# dp_tsc_com-v1_21.net
KiCad netlist of a schematic drawn in EAGLE
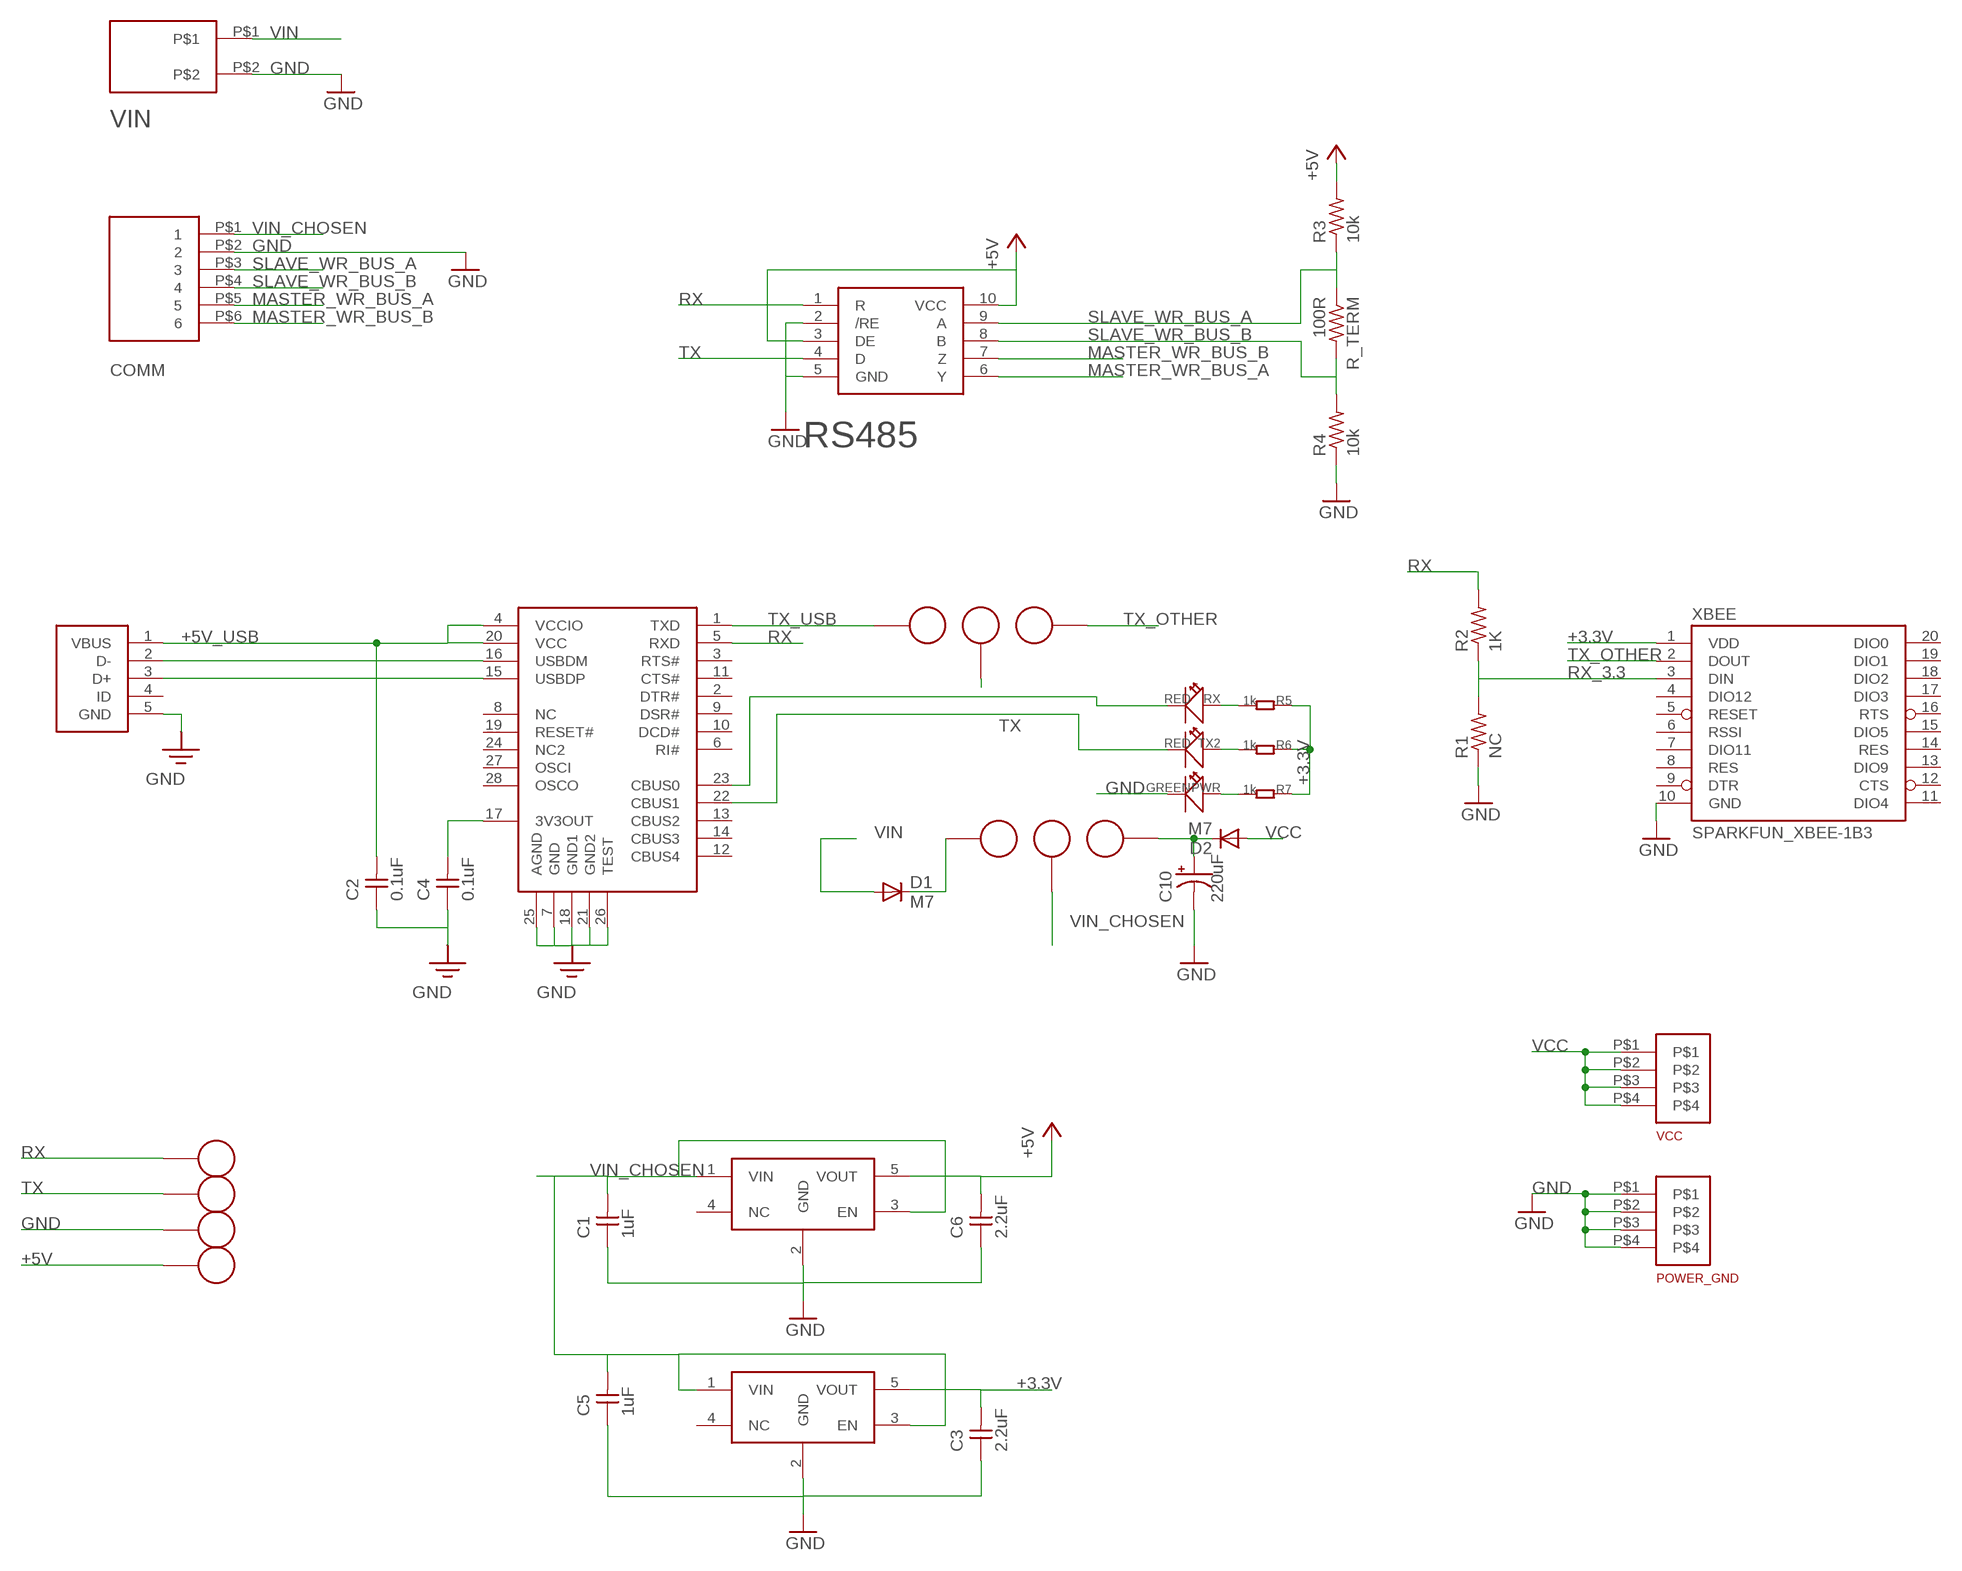
[diagram p0: schematic, sheet 1]

(export (version "E")
  (design (tool "Eeschema 10.0.6"))
  (components
    (comp (ref "+5V")
      (value "CONNECTOR_TV")
      (footprint "eagle-import:CONNECTOR_TV")
      (libsource (lib "eagle-import") (part "CONNECTOR_TV"))
    )
    (comp (ref "3.3V_REG")
      (value "MIC5235")
      (footprint "eagle-import:SOT-23-5")
      (libsource (lib "eagle-import") (part "MIC5235"))
    )
    (comp (ref "5V1")
      (value "CONNECTOR_TV")
      (footprint "eagle-import:CONNECTOR_TV")
      (libsource (lib "eagle-import") (part "CONNECTOR_TV"))
    )
    (comp (ref "5V_REG")
      (value "MIC5235")
      (footprint "eagle-import:SOT-23-5")
      (libsource (lib "eagle-import") (part "MIC5235"))
    )
    (comp (ref "5V_USB1")
      (value "CONNECTOR_TV")
      (footprint "eagle-import:CONNECTOR_TV")
      (libsource (lib "eagle-import") (part "CONNECTOR_TV"))
    )
    (comp (ref "5V_VREG1")
      (value "CONNECTOR_TV")
      (footprint "eagle-import:CONNECTOR_TV")
      (libsource (lib "eagle-import") (part "CONNECTOR_TV"))
    )
    (comp (ref "C1")
      (value "1uF")
      (footprint "eagle-import:0805@1")
      (libsource (lib "eagle-import") (part "CAPACITOR0805"))
    )
    (comp (ref "C2")
      (value "0.1uF")
      (footprint "eagle-import:0805@1")
      (libsource (lib "eagle-import") (part "CAPACITOR0805"))
    )
    (comp (ref "C3")
      (value "2.2uF")
      (footprint "eagle-import:0805@1")
      (libsource (lib "eagle-import") (part "CAPACITOR0805"))
    )
    (comp (ref "C4")
      (value "0.1uF")
      (footprint "eagle-import:0805@1")
      (libsource (lib "eagle-import") (part "CAPACITOR0805"))
    )
    (comp (ref "C5")
      (value "1uF")
      (footprint "eagle-import:0805@1")
      (libsource (lib "eagle-import") (part "CAPACITOR0805"))
    )
    (comp (ref "C6")
      (value "2.2uF")
      (footprint "eagle-import:0805@1")
      (libsource (lib "eagle-import") (part "CAPACITOR0805"))
    )
    (comp (ref "C10")
      (value "220uF")
      (footprint "eagle-import:HAO")
      (libsource (lib "eagle-import") (part "CAP-EMVY350ADA221MHA0G"))
    )
    (comp (ref "COMM")
      (value "6PIN-RIBBONCABLE-BOARDHEADER")
      (footprint "eagle-import:6PIN-HEADER-DUALROW")
      (libsource (lib "eagle-import") (part "6PIN-RIBBONCABLE-BOARDHEADER"))
    )
    (comp (ref "D1")
      (value "M7")
      (footprint "eagle-import:DO214BA")
      (libsource (lib "eagle-import") (part "DIODE-DO214BA"))
    )
    (comp (ref "D2")
      (value "M7")
      (footprint "eagle-import:DO214BA")
      (libsource (lib "eagle-import") (part "DIODE-DO214BA"))
    )
    (comp (ref "FT323R")
      (value "FT232R")
      (footprint "eagle-import:SSOP-28")
      (libsource (lib "eagle-import") (part "FT232R"))
    )
    (comp (ref "GND")
      (value "CONNECTOR_TV")
      (footprint "eagle-import:CONNECTOR_TV")
      (libsource (lib "eagle-import") (part "CONNECTOR_TV"))
    )
    (comp (ref "POWER_GND")
      (value "SCREW_TERMINAL_7700K")
      (footprint "eagle-import:SCREW_TERM_7700K")
      (libsource (lib "eagle-import") (part "SCREW_TERMINAL_7700K"))
    )
    (comp (ref "PWR")
      (value "GREEN")
      (footprint "eagle-import:LED0603_S")
      (libsource (lib "eagle-import") (part "LED0603_SS"))
    )
    (comp (ref "R1")
      (value "NC")
      (footprint "eagle-import:0603")
      (libsource (lib "eagle-import") (part "RESISTOR0603"))
    )
    (comp (ref "R2")
      (value "1K")
      (footprint "eagle-import:0603")
      (libsource (lib "eagle-import") (part "RESISTOR0603"))
    )
    (comp (ref "R3")
      (value "10k")
      (footprint "eagle-import:0603")
      (libsource (lib "eagle-import") (part "RESISTOR0603"))
    )
    (comp (ref "R4")
      (value "10k")
      (footprint "eagle-import:0603")
      (libsource (lib "eagle-import") (part "RESISTOR0603"))
    )
    (comp (ref "R5")
      (value "1k")
      (footprint "eagle-import:0603_S")
      (libsource (lib "eagle-import") (part "R0603_S"))
    )
    (comp (ref "R6")
      (value "1k")
      (footprint "eagle-import:0603_S")
      (libsource (lib "eagle-import") (part "R0603_S"))
    )
    (comp (ref "R7")
      (value "1k")
      (footprint "eagle-import:0603_S")
      (libsource (lib "eagle-import") (part "R0603_S"))
    )
    (comp (ref "RS485")
      (value "RS485-SN65HVD3086EDGSR")
      (footprint "eagle-import:MSOP-10")
      (libsource (lib "eagle-import") (part "RS485-SN65HVD3086EDGSR"))
    )
    (comp (ref "RX")
      (value "RED")
      (footprint "eagle-import:LED0603_S")
      (libsource (lib "eagle-import") (part "LED0603_SS"))
    )
    (comp (ref "RX1")
      (value "CONNECTOR_TV")
      (footprint "eagle-import:CONNECTOR_TV")
      (libsource (lib "eagle-import") (part "CONNECTOR_TV"))
    )
    (comp (ref "R_TERM")
      (value "100R")
      (footprint "eagle-import:0603")
      (libsource (lib "eagle-import") (part "RESISTOR0603"))
    )
    (comp (ref "TX")
      (value "CONNECTOR_TV")
      (footprint "eagle-import:CONNECTOR_TV")
      (libsource (lib "eagle-import") (part "CONNECTOR_TV"))
    )
    (comp (ref "TX1")
      (value "CONNECTOR_TV")
      (footprint "eagle-import:CONNECTOR_TV")
      (libsource (lib "eagle-import") (part "CONNECTOR_TV"))
    )
    (comp (ref "TX2")
      (value "RED")
      (footprint "eagle-import:LED0603_S")
      (libsource (lib "eagle-import") (part "LED0603_SS"))
    )
    (comp (ref "TX_FTDI")
      (value "CONNECTOR_TV")
      (footprint "eagle-import:CONNECTOR_TV")
      (libsource (lib "eagle-import") (part "CONNECTOR_TV"))
    )
    (comp (ref "TX_TTL")
      (value "CONNECTOR_TV")
      (footprint "eagle-import:CONNECTOR_TV")
      (libsource (lib "eagle-import") (part "CONNECTOR_TV"))
    )
    (comp (ref "USB")
      (value "MINIUSB")
      (footprint "eagle-import:UX60-MINI-USB")
      (libsource (lib "eagle-import") (part "MINIUSB"))
    )
    (comp (ref "VCC")
      (value "SCREW_TERMINAL_7700K")
      (footprint "eagle-import:SCREW_TERM_7700K")
      (libsource (lib "eagle-import") (part "SCREW_TERMINAL_7700K"))
    )
    (comp (ref "VIN")
      (value "2PIN-3.81MM-TERMINAL-BLOCK")
      (footprint "eagle-import:2PIN-TERMINAL-BLOCK-SMALLER")
      (libsource (lib "eagle-import") (part "2PIN-3.81MM-TERMINAL-BLOCK"))
    )
    (comp (ref "XBEE")
      (value "SPARKFUN_XBEE-1B3")
      (footprint "eagle-import:SPARKFUN_XBEE-SMD")
      (libsource (lib "eagle-import") (part "SPARKFUN_XBEE-1B3"))
    )
  )
  (nets
    (net (code "1") (name "+5V") (class "Default")
      (node (ref "+5V") (pin "P$1") (pinfunction "P$1_P$1") (pintype "bidirectional"))
      (node (ref "5V_REG") (pin "5") (pinfunction "VOUT_5") (pintype "bidirectional"))
      (node (ref "C6") (pin "2") (pinfunction "2_2") (pintype "passive"))
      (node (ref "R3") (pin "2") (pinfunction "2_2") (pintype "passive"))
      (node (ref "RS485") (pin "10") (pinfunction "VCC_10") (pintype "bidirectional"))
      (node (ref "RS485") (pin "3") (pinfunction "DE_3") (pintype "bidirectional"))
    )
    (net (code "2") (name "/+3.3V") (class "Default")
      (node (ref "3.3V_REG") (pin "5") (pinfunction "VOUT_5") (pintype "bidirectional"))
      (node (ref "C3") (pin "2") (pinfunction "2_2") (pintype "passive"))
      (node (ref "R5") (pin "1") (pinfunction "1_1") (pintype "bidirectional"))
      (node (ref "R6") (pin "1") (pinfunction "1_1") (pintype "bidirectional"))
      (node (ref "R7") (pin "1") (pinfunction "1_1") (pintype "bidirectional"))
      (node (ref "XBEE") (pin "1") (pinfunction "VDD_1") (pintype "power_in"))
    )
    (net (code "3") (name "/+5V_USB") (class "Default")
      (node (ref "C2") (pin "2") (pinfunction "2_2") (pintype "passive"))
      (node (ref "FT323R") (pin "20") (pinfunction "VCC_20") (pintype "bidirectional"))
      (node (ref "FT323R") (pin "4") (pinfunction "VCCIO_4") (pintype "bidirectional"))
      (node (ref "USB") (pin "1") (pinfunction "VBUS_1") (pintype "bidirectional"))
    )
    (net (code "4") (name "/MASTER_WR_BUS_A") (class "Default")
      (node (ref "COMM") (pin "P$5") (pinfunction "5_P$5") (pintype "bidirectional"))
      (node (ref "RS485") (pin "6") (pinfunction "Y_6") (pintype "bidirectional"))
    )
    (net (code "5") (name "/MASTER_WR_BUS_B") (class "Default")
      (node (ref "COMM") (pin "P$6") (pinfunction "6_P$6") (pintype "bidirectional"))
      (node (ref "RS485") (pin "7") (pinfunction "Z_7") (pintype "bidirectional"))
    )
    (net (code "6") (name "/RX") (class "Default")
      (node (ref "FT323R") (pin "5") (pinfunction "RXD_5") (pintype "bidirectional"))
      (node (ref "R2") (pin "2") (pinfunction "2_2") (pintype "passive"))
      (node (ref "RS485") (pin "1") (pinfunction "R_1") (pintype "bidirectional"))
      (node (ref "RX1") (pin "P$1") (pinfunction "P$1_P$1") (pintype "bidirectional"))
    )
    (net (code "7") (name "/RX_3.3") (class "Default")
      (node (ref "R1") (pin "2") (pinfunction "2_2") (pintype "passive"))
      (node (ref "R2") (pin "1") (pinfunction "1_1") (pintype "passive"))
      (node (ref "XBEE") (pin "3") (pinfunction "DIN_3") (pintype "input"))
    )
    (net (code "8") (name "/SLAVE_WR_BUS_A") (class "Default")
      (node (ref "COMM") (pin "P$3") (pinfunction "3_P$3") (pintype "bidirectional"))
      (node (ref "R3") (pin "1") (pinfunction "1_1") (pintype "passive"))
      (node (ref "RS485") (pin "9") (pinfunction "A_9") (pintype "bidirectional"))
      (node (ref "R_TERM") (pin "1") (pinfunction "1_1") (pintype "passive"))
    )
    (net (code "9") (name "/SLAVE_WR_BUS_B") (class "Default")
      (node (ref "COMM") (pin "P$4") (pinfunction "4_P$4") (pintype "bidirectional"))
      (node (ref "R4") (pin "2") (pinfunction "2_2") (pintype "passive"))
      (node (ref "RS485") (pin "8") (pinfunction "B_8") (pintype "bidirectional"))
      (node (ref "R_TERM") (pin "2") (pinfunction "2_2") (pintype "passive"))
    )
    (net (code "10") (name "/TX") (class "Default")
      (node (ref "RS485") (pin "4") (pinfunction "D_4") (pintype "bidirectional"))
      (node (ref "TX") (pin "P$1") (pinfunction "P$1_P$1") (pintype "bidirectional"))
      (node (ref "TX1") (pin "P$1") (pinfunction "P$1_P$1") (pintype "bidirectional"))
    )
    (net (code "11") (name "/TX_OTHER") (class "Default")
      (node (ref "TX_TTL") (pin "P$1") (pinfunction "P$1_P$1") (pintype "bidirectional"))
      (node (ref "XBEE") (pin "2") (pinfunction "DOUT_2") (pintype "output"))
    )
    (net (code "12") (name "/TX_USB") (class "Default")
      (node (ref "FT323R") (pin "1") (pinfunction "TXD_1") (pintype "bidirectional"))
      (node (ref "TX_FTDI") (pin "P$1") (pinfunction "P$1_P$1") (pintype "bidirectional"))
    )
    (net (code "13") (name "/VCC") (class "Default")
      (node (ref "D2") (pin "A") (pinfunction "A_A") (pintype "passive"))
      (node (ref "VCC") (pin "P$1") (pinfunction "P$1_P$1") (pintype "bidirectional"))
      (node (ref "VCC") (pin "P$2") (pinfunction "P$2_P$2") (pintype "bidirectional"))
      (node (ref "VCC") (pin "P$3") (pinfunction "P$3_P$3") (pintype "bidirectional"))
      (node (ref "VCC") (pin "P$4") (pinfunction "P$4_P$4") (pintype "bidirectional"))
    )
    (net (code "14") (name "/VIN") (class "Default")
      (node (ref "D1") (pin "A") (pinfunction "A_A") (pintype "passive"))
      (node (ref "VIN") (pin "P$1") (pinfunction "P$1_P$1") (pintype "bidirectional"))
    )
    (net (code "15") (name "/VIN_CHOSEN") (class "Default")
      (node (ref "3.3V_REG") (pin "1") (pinfunction "VIN_1") (pintype "bidirectional"))
      (node (ref "3.3V_REG") (pin "3") (pinfunction "EN_3") (pintype "bidirectional"))
      (node (ref "5V1") (pin "P$1") (pinfunction "P$1_P$1") (pintype "bidirectional"))
      (node (ref "5V_REG") (pin "1") (pinfunction "VIN_1") (pintype "bidirectional"))
      (node (ref "5V_REG") (pin "3") (pinfunction "EN_3") (pintype "bidirectional"))
      (node (ref "C1") (pin "2") (pinfunction "2_2") (pintype "passive"))
      (node (ref "C5") (pin "2") (pinfunction "2_2") (pintype "passive"))
      (node (ref "COMM") (pin "P$1") (pinfunction "1_P$1") (pintype "bidirectional"))
    )
    (net (code "16") (name "GND") (class "Default")
      (node (ref "3.3V_REG") (pin "2") (pinfunction "GND_2") (pintype "bidirectional"))
      (node (ref "5V_REG") (pin "2") (pinfunction "GND_2") (pintype "bidirectional"))
      (node (ref "C1") (pin "1") (pinfunction "1_1") (pintype "passive"))
      (node (ref "C10") (pin "-") (pinfunction "-_-") (pintype "passive"))
      (node (ref "C2") (pin "1") (pinfunction "1_1") (pintype "passive"))
      (node (ref "C3") (pin "1") (pinfunction "1_1") (pintype "passive"))
      (node (ref "C4") (pin "1") (pinfunction "1_1") (pintype "passive"))
      (node (ref "C5") (pin "1") (pinfunction "1_1") (pintype "passive"))
      (node (ref "C6") (pin "1") (pinfunction "1_1") (pintype "passive"))
      (node (ref "COMM") (pin "P$2") (pinfunction "2_P$2") (pintype "bidirectional"))
      (node (ref "FT323R") (pin "18") (pinfunction "GND1_18") (pintype "bidirectional"))
      (node (ref "FT323R") (pin "21") (pinfunction "GND2_21") (pintype "bidirectional"))
      (node (ref "FT323R") (pin "25") (pinfunction "AGND_25") (pintype "bidirectional"))
      (node (ref "FT323R") (pin "26") (pinfunction "TEST_26") (pintype "bidirectional"))
      (node (ref "FT323R") (pin "7") (pinfunction "GND_7") (pintype "bidirectional"))
      (node (ref "GND") (pin "P$1") (pinfunction "P$1_P$1") (pintype "bidirectional"))
      (node (ref "POWER_GND") (pin "P$1") (pinfunction "P$1_P$1") (pintype "bidirectional"))
      (node (ref "POWER_GND") (pin "P$2") (pinfunction "P$2_P$2") (pintype "bidirectional"))
      (node (ref "POWER_GND") (pin "P$3") (pinfunction "P$3_P$3") (pintype "bidirectional"))
      (node (ref "POWER_GND") (pin "P$4") (pinfunction "P$4_P$4") (pintype "bidirectional"))
      (node (ref "PWR") (pin "2") (pinfunction "-_2") (pintype "bidirectional"))
      (node (ref "R1") (pin "1") (pinfunction "1_1") (pintype "passive"))
      (node (ref "R4") (pin "1") (pinfunction "1_1") (pintype "passive"))
      (node (ref "RS485") (pin "2") (pinfunction "/RE_2") (pintype "bidirectional"))
      (node (ref "RS485") (pin "5") (pinfunction "GND_5") (pintype "bidirectional"))
      (node (ref "USB") (pin "5") (pinfunction "GND_5") (pintype "bidirectional"))
      (node (ref "VIN") (pin "P$2") (pinfunction "P$2_P$2") (pintype "bidirectional"))
      (node (ref "XBEE") (pin "10") (pinfunction "GND_10") (pintype "power_in"))
    )
    (net (code "17") (name "Net-(5V_USB1-PadP$1)") (class "Default")
      (node (ref "5V_USB1") (pin "P$1") (pinfunction "P$1_P$1") (pintype "bidirectional"))
      (node (ref "C10") (pin "+") (pinfunction "+_+") (pintype "passive"))
      (node (ref "D2") (pin "C") (pinfunction "C_C") (pintype "passive"))
    )
    (net (code "18") (name "Net-(5V_VREG1-PadP$1)") (class "Default")
      (node (ref "5V_VREG1") (pin "P$1") (pinfunction "P$1_P$1") (pintype "bidirectional"))
      (node (ref "D1") (pin "C") (pinfunction "C_C") (pintype "passive"))
    )
    (net (code "19") (name "Net-(FT323R-3V3OUT)") (class "Default")
      (node (ref "C4") (pin "2") (pinfunction "2_2") (pintype "passive"))
      (node (ref "FT323R") (pin "17") (pinfunction "3V3OUT_17") (pintype "bidirectional"))
    )
    (net (code "20") (name "Net-(FT323R-CBUS0)") (class "Default")
      (node (ref "FT323R") (pin "23") (pinfunction "CBUS0_23") (pintype "bidirectional"))
      (node (ref "RX") (pin "2") (pinfunction "-_2") (pintype "bidirectional"))
    )
    (net (code "21") (name "Net-(FT323R-CBUS1)") (class "Default")
      (node (ref "FT323R") (pin "22") (pinfunction "CBUS1_22") (pintype "bidirectional"))
      (node (ref "TX2") (pin "2") (pinfunction "-_2") (pintype "bidirectional"))
    )
    (net (code "22") (name "Net-(FT323R-USBDM)") (class "Default")
      (node (ref "FT323R") (pin "16") (pinfunction "USBDM_16") (pintype "bidirectional"))
      (node (ref "USB") (pin "2") (pinfunction "D-_2") (pintype "bidirectional"))
    )
    (net (code "23") (name "Net-(FT323R-USBDP)") (class "Default")
      (node (ref "FT323R") (pin "15") (pinfunction "USBDP_15") (pintype "bidirectional"))
      (node (ref "USB") (pin "3") (pinfunction "D+_3") (pintype "bidirectional"))
    )
    (net (code "24") (name "Net-(PWR-+)") (class "Default")
      (node (ref "PWR") (pin "1") (pinfunction "+_1") (pintype "bidirectional"))
      (node (ref "R7") (pin "2") (pinfunction "2_2") (pintype "bidirectional"))
    )
    (net (code "25") (name "Net-(RX-+)") (class "Default")
      (node (ref "R5") (pin "2") (pinfunction "2_2") (pintype "bidirectional"))
      (node (ref "RX") (pin "1") (pinfunction "+_1") (pintype "bidirectional"))
    )
    (net (code "26") (name "Net-(TX2-+)") (class "Default")
      (node (ref "R6") (pin "2") (pinfunction "2_2") (pintype "bidirectional"))
      (node (ref "TX2") (pin "1") (pinfunction "+_1") (pintype "bidirectional"))
    )
    (net (code "27") (name "unconnected-(3.3V_REG-NC-Pad4)") (class "Default")
      (node (ref "3.3V_REG") (pin "4") (pinfunction "NC_4") (pintype "bidirectional"))
    )
    (net (code "28") (name "unconnected-(5V_REG-NC-Pad4)") (class "Default")
      (node (ref "5V_REG") (pin "4") (pinfunction "NC_4") (pintype "bidirectional"))
    )
    (net (code "29") (name "unconnected-(FT323R-CBUS2-Pad13)") (class "Default")
      (node (ref "FT323R") (pin "13") (pinfunction "CBUS2_13") (pintype "bidirectional"))
    )
    (net (code "30") (name "unconnected-(FT323R-CBUS3-Pad14)") (class "Default")
      (node (ref "FT323R") (pin "14") (pinfunction "CBUS3_14") (pintype "bidirectional"))
    )
    (net (code "31") (name "unconnected-(FT323R-CBUS4-Pad12)") (class "Default")
      (node (ref "FT323R") (pin "12") (pinfunction "CBUS4_12") (pintype "bidirectional"))
    )
    (net (code "32") (name "unconnected-(FT323R-CTS#-Pad11)") (class "Default")
      (node (ref "FT323R") (pin "11") (pinfunction "CTS#_11") (pintype "bidirectional"))
    )
    (net (code "33") (name "unconnected-(FT323R-DCD#-Pad10)") (class "Default")
      (node (ref "FT323R") (pin "10") (pinfunction "DCD#_10") (pintype "bidirectional"))
    )
    (net (code "34") (name "unconnected-(FT323R-DSR#-Pad9)") (class "Default")
      (node (ref "FT323R") (pin "9") (pinfunction "DSR#_9") (pintype "bidirectional"))
    )
    (net (code "35") (name "unconnected-(FT323R-DTR#-Pad2)") (class "Default")
      (node (ref "FT323R") (pin "2") (pinfunction "DTR#_2") (pintype "bidirectional"))
    )
    (net (code "36") (name "unconnected-(FT323R-NC-Pad8)") (class "Default")
      (node (ref "FT323R") (pin "8") (pinfunction "NC_8") (pintype "bidirectional"))
    )
    (net (code "37") (name "unconnected-(FT323R-NC2-Pad24)") (class "Default")
      (node (ref "FT323R") (pin "24") (pinfunction "NC2_24") (pintype "bidirectional"))
    )
    (net (code "38") (name "unconnected-(FT323R-OSCI-Pad27)") (class "Default")
      (node (ref "FT323R") (pin "27") (pinfunction "OSCI_27") (pintype "bidirectional"))
    )
    (net (code "39") (name "unconnected-(FT323R-OSCO-Pad28)") (class "Default")
      (node (ref "FT323R") (pin "28") (pinfunction "OSCO_28") (pintype "bidirectional"))
    )
    (net (code "40") (name "unconnected-(FT323R-RESET#-Pad19)") (class "Default")
      (node (ref "FT323R") (pin "19") (pinfunction "RESET#_19") (pintype "bidirectional"))
    )
    (net (code "41") (name "unconnected-(FT323R-RI#-Pad6)") (class "Default")
      (node (ref "FT323R") (pin "6") (pinfunction "RI#_6") (pintype "bidirectional"))
    )
    (net (code "42") (name "unconnected-(FT323R-RTS#-Pad3)") (class "Default")
      (node (ref "FT323R") (pin "3") (pinfunction "RTS#_3") (pintype "bidirectional"))
    )
    (net (code "43") (name "unconnected-(USB-ID-Pad4)") (class "Default")
      (node (ref "USB") (pin "4") (pinfunction "ID_4") (pintype "bidirectional"))
    )
    (net (code "44") (name "unconnected-(XBEE-CTS-Pad12)") (class "Default")
      (node (ref "XBEE") (pin "12") (pinfunction "CTS_12") (pintype "output"))
    )
    (net (code "45") (name "unconnected-(XBEE-DIO0-Pad20)") (class "Default")
      (node (ref "XBEE") (pin "20") (pinfunction "DIO0_20") (pintype "bidirectional"))
    )
    (net (code "46") (name "unconnected-(XBEE-DIO1-Pad19)") (class "Default")
      (node (ref "XBEE") (pin "19") (pinfunction "DIO1_19") (pintype "bidirectional"))
    )
    (net (code "47") (name "unconnected-(XBEE-DIO2-Pad18)") (class "Default")
      (node (ref "XBEE") (pin "18") (pinfunction "DIO2_18") (pintype "bidirectional"))
    )
    (net (code "48") (name "unconnected-(XBEE-DIO3-Pad17)") (class "Default")
      (node (ref "XBEE") (pin "17") (pinfunction "DIO3_17") (pintype "bidirectional"))
    )
    (net (code "49") (name "unconnected-(XBEE-DIO4-Pad11)") (class "Default")
      (node (ref "XBEE") (pin "11") (pinfunction "DIO4_11") (pintype "bidirectional"))
    )
    (net (code "50") (name "unconnected-(XBEE-DIO5-Pad15)") (class "Default")
      (node (ref "XBEE") (pin "15") (pinfunction "DIO5_15") (pintype "bidirectional"))
    )
    (net (code "51") (name "unconnected-(XBEE-DIO9-Pad13)") (class "Default")
      (node (ref "XBEE") (pin "13") (pinfunction "DIO9_13") (pintype "bidirectional"))
    )
    (net (code "52") (name "unconnected-(XBEE-DIO11-Pad7)") (class "Default")
      (node (ref "XBEE") (pin "7") (pinfunction "DIO11_7") (pintype "bidirectional"))
    )
    (net (code "53") (name "unconnected-(XBEE-DIO12-Pad4)") (class "Default")
      (node (ref "XBEE") (pin "4") (pinfunction "DIO12_4") (pintype "bidirectional"))
    )
    (net (code "54") (name "unconnected-(XBEE-DTR-Pad9)") (class "Default")
      (node (ref "XBEE") (pin "9") (pinfunction "DTR_9") (pintype "bidirectional"))
    )
    (net (code "55") (name "unconnected-(XBEE-RES-Pad8)") (class "Default")
      (node (ref "XBEE") (pin "8") (pinfunction "RES_8") (pintype "bidirectional"))
    )
    (net (code "56") (name "unconnected-(XBEE-RES-Pad14)") (class "Default")
      (node (ref "XBEE") (pin "14") (pinfunction "RES_14") (pintype "bidirectional"))
    )
    (net (code "57") (name "unconnected-(XBEE-RESET-Pad5)") (class "Default")
      (node (ref "XBEE") (pin "5") (pinfunction "RESET_5") (pintype "input"))
    )
    (net (code "58") (name "unconnected-(XBEE-RSSI-Pad6)") (class "Default")
      (node (ref "XBEE") (pin "6") (pinfunction "RSSI_6") (pintype "bidirectional"))
    )
    (net (code "59") (name "unconnected-(XBEE-RTS-Pad16)") (class "Default")
      (node (ref "XBEE") (pin "16") (pinfunction "RTS_16") (pintype "input"))
    )
  )
)
